# Supply_Lines.net
KiCad netlist of a schematic drawn in Altium Designer
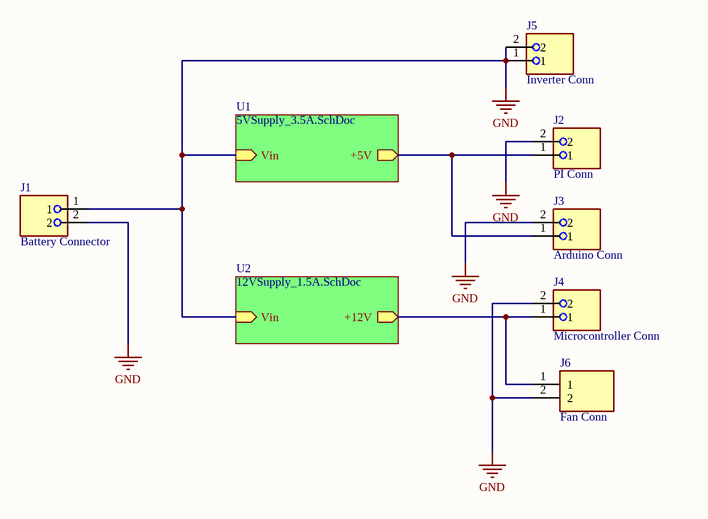
[diagram p0: Supply Lines.SchDoc]

(export (version "E")
  (design (tool "Eeschema 10.0.6"))
  (components
    (comp (ref "J1")
      (value "Battery Connector")
      (footprint "PHOENIX_1902547")
      (description "Conn PC Terminal Block 2 POS 9.52mm Solder ST Thru-Hole 32A Cardboard")
      (fields
        (field (name "MANUFACTURER") "Phoenix Contact")
        (field (name "MANUFACTURER PART NUMBER") "1902547")
      )
      (libsource (lib "") (part "1902547_1"))
    )
    (comp (ref "J2")
      (value "PI Conn")
      (footprint "PHOENIX_1902547")
      (description "Conn PC Terminal Block 2 POS 9.52mm Solder ST Thru-Hole 32A Cardboard")
      (fields
        (field (name "MANUFACTURER") "Phoenix Contact")
        (field (name "MANUFACTURER PART NUMBER") "1902547")
      )
      (libsource (lib "Supply Lines") (part "1902547"))
    )
    (comp (ref "J3")
      (value "Arduino Conn")
      (footprint "PHOENIX_1902547")
      (description "Conn PC Terminal Block 2 POS 9.52mm Solder ST Thru-Hole 32A Cardboard")
      (fields
        (field (name "MANUFACTURER") "Phoenix Contact")
        (field (name "MANUFACTURER PART NUMBER") "1902547")
      )
      (libsource (lib "Supply Lines") (part "1902547"))
    )
    (comp (ref "J4")
      (value "Microcontroller Conn")
      (footprint "PHOENIX_1902547")
      (description "Conn PC Terminal Block 2 POS 9.52mm Solder ST Thru-Hole 32A Cardboard")
      (fields
        (field (name "MANUFACTURER") "Phoenix Contact")
        (field (name "MANUFACTURER PART NUMBER") "1902547")
      )
      (libsource (lib "Supply Lines") (part "1902547"))
    )
    (comp (ref "J5")
      (value "Inverter Conn")
      (footprint "PHOENIX_1902547")
      (description "Conn PC Terminal Block 2 POS 9.52mm Solder ST Thru-Hole 32A Cardboard")
      (fields
        (field (name "MANUFACTURER") "Phoenix Contact")
        (field (name "MANUFACTURER PART NUMBER") "1902547")
      )
      (libsource (lib "Supply Lines") (part "1902547"))
    )
    (comp (ref "J6")
      (value "Fan Conn")
      (footprint "1935776")
      (description "Conn Terminal Block 2 POS 5mm Solder ST Thru-Hole 32ACardboard")
      (fields
        (field (name "MANUFACTURER") "Phoenix Contact")
        (field (name "MANUFACTURER PART NUMBER") "1935776")
      )
      (libsource (lib "Supply Lines") (part "1935776"))
    )
  )
  (nets
    (net (code "1") (name "/+5V") (class "Default")
      (node (ref "J2") (pin "1") (pinfunction "1_1") (pintype "passive"))
      (node (ref "J3") (pin "1") (pinfunction "1_1") (pintype "passive"))
    )
    (net (code "2") (name "/+12V") (class "Default")
      (node (ref "J4") (pin "1") (pinfunction "1_1") (pintype "passive"))
      (node (ref "J6") (pin "1") (pinfunction "1_1") (pintype "passive"))
    )
    (net (code "3") (name "GND") (class "Default")
      (node (ref "J1") (pin "1") (pinfunction "1_1") (pintype "passive"))
      (node (ref "J1") (pin "2") (pinfunction "2_2") (pintype "passive"))
      (node (ref "J2") (pin "2") (pinfunction "2_2") (pintype "passive"))
      (node (ref "J3") (pin "2") (pinfunction "2_2") (pintype "passive"))
      (node (ref "J4") (pin "2") (pinfunction "2_2") (pintype "passive"))
      (node (ref "J5") (pin "1") (pinfunction "1_1") (pintype "passive"))
      (node (ref "J5") (pin "2") (pinfunction "2_2") (pintype "passive"))
      (node (ref "J6") (pin "2") (pinfunction "2_2") (pintype "passive"))
    )
  )
)
